# HDMI_IN.net
KiCad netlist of a schematic drawn in Altium Designer
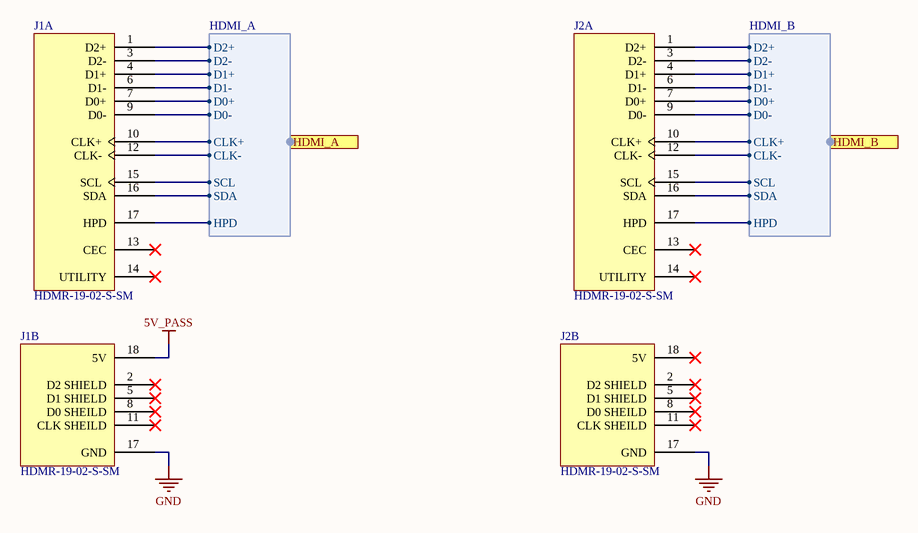
[diagram p0: HDMI_IN.SchDoc]

(export (version "E")
  (design (tool "Eeschema 10.0.6"))
  (components
    (comp (ref "J1")
      (value "HDMR-19-02-S-SM")
      (footprint "SAMTEC_HDMR-19-02-S-SM")
      (description "Conn HDMI RCP 19 POS 0.5mm Solder RA SMD 19 Terminal 1 Port")
      (libsource (lib "KVM Library") (part "SAMTEC_HDMR-19-02-S-SM"))
    )
    (comp (ref "J2")
      (value "HDMR-19-02-S-SM")
      (footprint "SAMTEC_HDMR-19-02-S-SM")
      (description "Conn HDMI RCP 19 POS 0.5mm Solder RA SMD 19 Terminal 1 Port")
      (libsource (lib "KVM Symbols") (part "SAMTEC_HDMR-19-02-S-SM"))
    )
  )
  (nets
    (net (code "5") (name "5V_PASS") (class "Default")
      (node (ref "J1") (pin "18") (pinfunction "5V_18") (pintype "power_in"))
    )
    (net (code "6") (name "GND") (class "Default")
      (node (ref "J1") (pin "17") (pinfunction "GND_17") (pintype "passive"))
      (node (ref "J2") (pin "17") (pinfunction "GND_17") (pintype "passive"))
    )
    (net (code "7") (name "unconnected-(J1A-CEC-Pad13)") (class "Default")
      (node (ref "J1") (pin "13") (pinfunction "CEC_13") (pintype "passive+no_connect"))
    )
    (net (code "8") (name "unconnected-(J1A-CLK+-Pad10)") (class "Default")
      (node (ref "J1") (pin "10") (pinfunction "CLK+_10") (pintype "passive"))
    )
    (net (code "9") (name "unconnected-(J1A-CLK--Pad12)") (class "Default")
      (node (ref "J1") (pin "12") (pinfunction "CLK-_12") (pintype "passive"))
    )
    (net (code "10") (name "unconnected-(J1A-D0+-Pad7)") (class "Default")
      (node (ref "J1") (pin "7") (pinfunction "D0+_7") (pintype "passive"))
    )
    (net (code "11") (name "unconnected-(J1A-D0--Pad9)") (class "Default")
      (node (ref "J1") (pin "9") (pinfunction "D0-_9") (pintype "passive"))
    )
    (net (code "12") (name "unconnected-(J1A-D1+-Pad4)") (class "Default")
      (node (ref "J1") (pin "4") (pinfunction "D1+_4") (pintype "passive"))
    )
    (net (code "13") (name "unconnected-(J1A-D1--Pad6)") (class "Default")
      (node (ref "J1") (pin "6") (pinfunction "D1-_6") (pintype "passive"))
    )
    (net (code "14") (name "unconnected-(J1A-D2+-Pad1)") (class "Default")
      (node (ref "J1") (pin "1") (pinfunction "D2+_1") (pintype "passive"))
    )
    (net (code "15") (name "unconnected-(J1A-D2--Pad3)") (class "Default")
      (node (ref "J1") (pin "3") (pinfunction "D2-_3") (pintype "passive"))
    )
    (net (code "16") (name "unconnected-(J1A-HPD-Pad17)") (class "Default")
      (node (ref "J1") (pin "17") (pinfunction "HPD_17") (pintype "passive"))
    )
    (net (code "17") (name "unconnected-(J1A-SCL-Pad15)") (class "Default")
      (node (ref "J1") (pin "15") (pinfunction "SCL_15") (pintype "passive"))
    )
    (net (code "18") (name "unconnected-(J1A-SDA-Pad16)") (class "Default")
      (node (ref "J1") (pin "16") (pinfunction "SDA_16") (pintype "passive"))
    )
    (net (code "19") (name "unconnected-(J1A-UTILITY-Pad14)") (class "Default")
      (node (ref "J1") (pin "14") (pinfunction "UTILITY_14") (pintype "passive+no_connect"))
    )
    (net (code "20") (name "unconnected-(J1B-CLK_SHEILD-Pad11)") (class "Default")
      (node (ref "J1") (pin "11") (pinfunction "CLK_SHEILD_11") (pintype "passive+no_connect"))
    )
    (net (code "21") (name "unconnected-(J1B-D0_SHEILD-Pad8)") (class "Default")
      (node (ref "J1") (pin "8") (pinfunction "D0_SHEILD_8") (pintype "passive+no_connect"))
    )
    (net (code "22") (name "unconnected-(J1B-D1_SHIELD-Pad5)") (class "Default")
      (node (ref "J1") (pin "5") (pinfunction "D1_SHIELD_5") (pintype "passive+no_connect"))
    )
    (net (code "23") (name "unconnected-(J1B-D2_SHIELD-Pad2)") (class "Default")
      (node (ref "J1") (pin "2") (pinfunction "D2_SHIELD_2") (pintype "passive+no_connect"))
    )
    (net (code "24") (name "unconnected-(J2A-CEC-Pad13)") (class "Default")
      (node (ref "J2") (pin "13") (pinfunction "CEC_13") (pintype "passive+no_connect"))
    )
    (net (code "25") (name "unconnected-(J2A-CLK+-Pad10)") (class "Default")
      (node (ref "J2") (pin "10") (pinfunction "CLK+_10") (pintype "passive"))
    )
    (net (code "26") (name "unconnected-(J2A-CLK--Pad12)") (class "Default")
      (node (ref "J2") (pin "12") (pinfunction "CLK-_12") (pintype "passive"))
    )
    (net (code "27") (name "unconnected-(J2A-D0+-Pad7)") (class "Default")
      (node (ref "J2") (pin "7") (pinfunction "D0+_7") (pintype "passive"))
    )
    (net (code "28") (name "unconnected-(J2A-D0--Pad9)") (class "Default")
      (node (ref "J2") (pin "9") (pinfunction "D0-_9") (pintype "passive"))
    )
    (net (code "29") (name "unconnected-(J2A-D1+-Pad4)") (class "Default")
      (node (ref "J2") (pin "4") (pinfunction "D1+_4") (pintype "passive"))
    )
    (net (code "30") (name "unconnected-(J2A-D1--Pad6)") (class "Default")
      (node (ref "J2") (pin "6") (pinfunction "D1-_6") (pintype "passive"))
    )
    (net (code "31") (name "unconnected-(J2A-D2+-Pad1)") (class "Default")
      (node (ref "J2") (pin "1") (pinfunction "D2+_1") (pintype "passive"))
    )
    (net (code "32") (name "unconnected-(J2A-D2--Pad3)") (class "Default")
      (node (ref "J2") (pin "3") (pinfunction "D2-_3") (pintype "passive"))
    )
    (net (code "33") (name "unconnected-(J2A-HPD-Pad17)") (class "Default")
      (node (ref "J2") (pin "17") (pinfunction "HPD_17") (pintype "passive"))
    )
    (net (code "34") (name "unconnected-(J2A-SCL-Pad15)") (class "Default")
      (node (ref "J2") (pin "15") (pinfunction "SCL_15") (pintype "passive"))
    )
    (net (code "35") (name "unconnected-(J2A-SDA-Pad16)") (class "Default")
      (node (ref "J2") (pin "16") (pinfunction "SDA_16") (pintype "passive"))
    )
    (net (code "36") (name "unconnected-(J2A-UTILITY-Pad14)") (class "Default")
      (node (ref "J2") (pin "14") (pinfunction "UTILITY_14") (pintype "passive+no_connect"))
    )
    (net (code "37") (name "unconnected-(J2B-5V-Pad18)") (class "Default")
      (node (ref "J2") (pin "18") (pinfunction "5V_18") (pintype "power_in+no_connect"))
    )
    (net (code "38") (name "unconnected-(J2B-CLK_SHEILD-Pad11)") (class "Default")
      (node (ref "J2") (pin "11") (pinfunction "CLK_SHEILD_11") (pintype "passive+no_connect"))
    )
    (net (code "39") (name "unconnected-(J2B-D0_SHEILD-Pad8)") (class "Default")
      (node (ref "J2") (pin "8") (pinfunction "D0_SHEILD_8") (pintype "passive+no_connect"))
    )
    (net (code "40") (name "unconnected-(J2B-D1_SHIELD-Pad5)") (class "Default")
      (node (ref "J2") (pin "5") (pinfunction "D1_SHIELD_5") (pintype "passive+no_connect"))
    )
    (net (code "41") (name "unconnected-(J2B-D2_SHIELD-Pad2)") (class "Default")
      (node (ref "J2") (pin "2") (pinfunction "D2_SHIELD_2") (pintype "passive+no_connect"))
    )
  )
)
